# pwrconv.net
KiCad netlist of a schematic drawn in Altium Designer
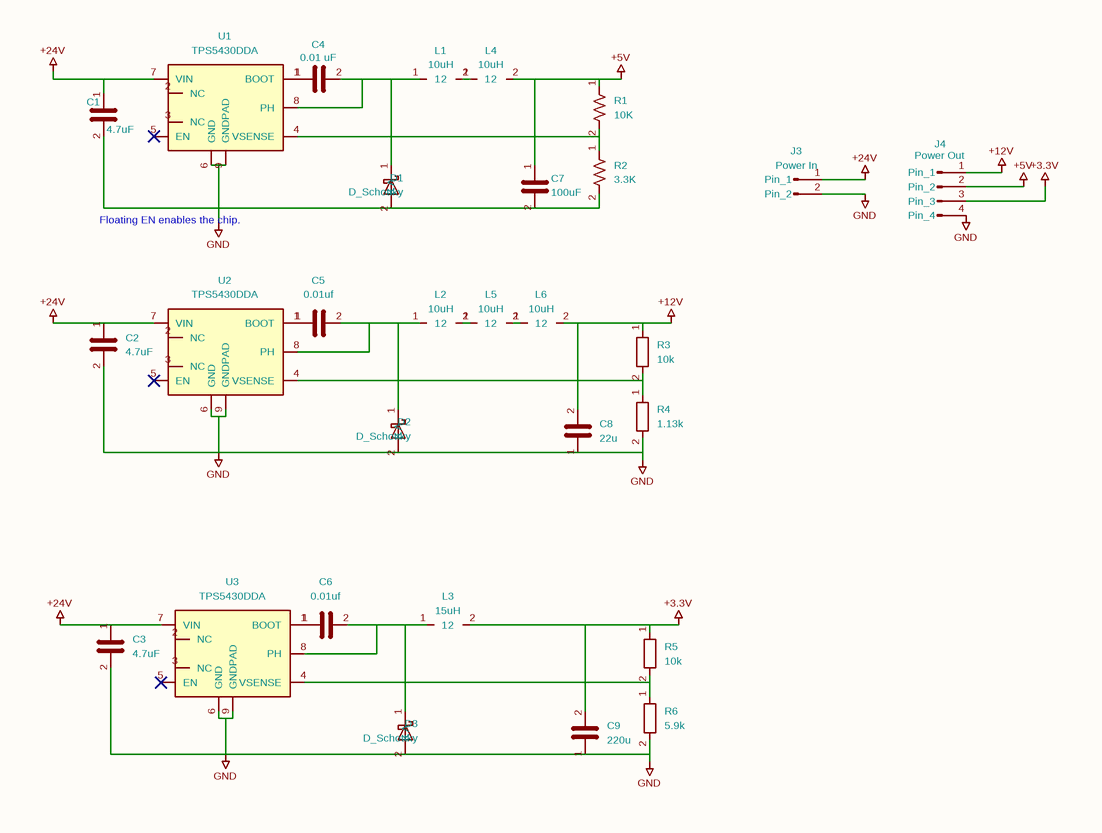
[diagram p0: pwrconv.SchDoc]

(export (version "E")
  (design (tool "Eeschema 10.0.6"))
  (components
    (comp (ref "C1")
      (value "4.7uF")
      (description "Unpolarized capacitor")
      (libsource (lib "Device") (part "C"))
    )
    (comp (ref "C2")
      (value "4.7uF")
      (description "Unpolarized Capacitor")
      (libsource (lib "Device") (part "C"))
    )
    (comp (ref "C3")
      (value "4.7uF")
      (description "Unpolarized Capacitor")
      (libsource (lib "Device") (part "C"))
    )
    (comp (ref "C4")
      (value "0.01 uF")
      (description "Unpolarized capacitor")
      (libsource (lib "Device") (part "C"))
    )
    (comp (ref "C5") (value "0.01uf") (libsource (lib "Device") (part "C")))
    (comp (ref "C6") (value "0.01uf") (libsource (lib "Device") (part "C")))
    (comp (ref "C7")
      (value "100uF")
      (description "Unpolarized capacitor")
      (libsource (lib "Device") (part "C"))
    )
    (comp (ref "C8") (value "22u") (libsource (lib "Device") (part "C")))
    (comp (ref "C9") (value "220u") (libsource (lib "Device") (part "C")))
    (comp (ref "D1")
      (value "D_Schottky")
      (description "Schottky diode")
      (libsource (lib "Device") (part "D_Schottky"))
    )
    (comp (ref "D2")
      (value "D_Schottky")
      (description "Schottky diode")
      (libsource (lib "Device") (part "D_Schottky"))
    )
    (comp (ref "D3")
      (value "D_Schottky")
      (description "Schottky diode")
      (libsource (lib "Device") (part "D_Schottky"))
    )
    (comp (ref "J3")
      (value "Power In")
      (description "Generic connector, single row, 01x02, script generated")
      (libsource (lib "Connector") (part "Conn_01x02_Pin"))
    )
    (comp (ref "J4")
      (value "Power Out")
      (description "Generic connector, single row, 01x04, script generated")
      (libsource (lib "Connector") (part "Conn_01x04_Pin"))
    )
    (comp (ref "L1") (value "10uH") (libsource (lib "Device") (part "L")))
    (comp (ref "L2") (value "10uH") (libsource (lib "Device") (part "L")))
    (comp (ref "L3") (value "15uH") (libsource (lib "Device") (part "L")))
    (comp (ref "L4") (value "10uH") (libsource (lib "Device") (part "L")))
    (comp (ref "L5") (value "10uH") (libsource (lib "Device") (part "L")))
    (comp (ref "L6") (value "10uH") (libsource (lib "Device") (part "L")))
    (comp (ref "R1")
      (value "10K")
      (description "Resistor, US symbol")
      (libsource (lib "Device") (part "R_US"))
    )
    (comp (ref "R2")
      (value "3.3K")
      (description "Resistor, US symbol")
      (libsource (lib "Device") (part "R_US"))
    )
    (comp (ref "R3") (value "10k") (libsource (lib "Device") (part "R")))
    (comp (ref "R4") (value "1.13k") (libsource (lib "Device") (part "R")))
    (comp (ref "R5") (value "10k") (libsource (lib "Device") (part "R")))
    (comp (ref "R6") (value "5.9k") (libsource (lib "Device") (part "R")))
    (comp (ref "U1")
      (value "TPS5430DDA")
      (description "3A, Step Down Swift Converter, Adjustable Output Voltage, 5.5-36V Input Voltage, PowerSO-8")
      (libsource (lib "Regulator_Switching") (part "TPS5430DDA"))
    )
    (comp (ref "U2") (value "TPS5430DDA") (libsource (lib "Regulator_Switching") (part "TPS5430DDA")))
    (comp (ref "U3") (value "TPS5430DDA") (libsource (lib "Regulator_Switching") (part "TPS5430DDA")))
  )
  (nets
    (net (code "1") (name "+3.3V") (class "Default")
      (node (ref "C9") (pin "2") (pinfunction "2_2") (pintype "passive"))
      (node (ref "J4") (pin "3") (pinfunction "Pin_3_3") (pintype "passive"))
      (node (ref "L3") (pin "2") (pinfunction "2_2") (pintype "passive"))
      (node (ref "R5") (pin "1") (pinfunction "1_1") (pintype "passive"))
    )
    (net (code "2") (name "+5V") (class "Default")
      (node (ref "C7") (pin "1") (pinfunction "1_1") (pintype "passive"))
      (node (ref "J4") (pin "2") (pinfunction "Pin_2_2") (pintype "passive"))
      (node (ref "L4") (pin "2") (pinfunction "2_2") (pintype "passive"))
      (node (ref "R1") (pin "1") (pinfunction "1_1") (pintype "passive"))
    )
    (net (code "3") (name "+12V") (class "Default")
      (node (ref "C8") (pin "2") (pinfunction "2_2") (pintype "passive"))
      (node (ref "J4") (pin "1") (pinfunction "Pin_1_1") (pintype "passive"))
      (node (ref "L6") (pin "2") (pinfunction "2_2") (pintype "passive"))
      (node (ref "R3") (pin "1") (pinfunction "1_1") (pintype "passive"))
    )
    (net (code "4") (name "+24V") (class "Default")
      (node (ref "C1") (pin "1") (pinfunction "1_1") (pintype "passive"))
      (node (ref "C2") (pin "1") (pinfunction "1_1") (pintype "passive"))
      (node (ref "C3") (pin "1") (pinfunction "1_1") (pintype "passive"))
      (node (ref "J3") (pin "1") (pinfunction "Pin_1_1") (pintype "passive"))
      (node (ref "U1") (pin "7") (pinfunction "VIN_7") (pintype "passive"))
      (node (ref "U2") (pin "7") (pinfunction "VIN_7") (pintype "passive"))
      (node (ref "U3") (pin "7") (pinfunction "VIN_7") (pintype "passive"))
    )
    (net (code "5") (name "GND") (class "Default")
      (node (ref "C1") (pin "2") (pinfunction "2_2") (pintype "passive"))
      (node (ref "C2") (pin "2") (pinfunction "2_2") (pintype "passive"))
      (node (ref "C3") (pin "2") (pinfunction "2_2") (pintype "passive"))
      (node (ref "C7") (pin "2") (pinfunction "2_2") (pintype "passive"))
      (node (ref "C8") (pin "1") (pinfunction "1_1") (pintype "passive"))
      (node (ref "C9") (pin "1") (pinfunction "1_1") (pintype "passive"))
      (node (ref "D1") (pin "2") (pinfunction "A_2") (pintype "passive"))
      (node (ref "D2") (pin "2") (pinfunction "A_2") (pintype "passive"))
      (node (ref "D3") (pin "2") (pinfunction "A_2") (pintype "passive"))
      (node (ref "J3") (pin "2") (pinfunction "Pin_2_2") (pintype "passive"))
      (node (ref "J4") (pin "4") (pinfunction "Pin_4_4") (pintype "passive"))
      (node (ref "R2") (pin "2") (pinfunction "2_2") (pintype "passive"))
      (node (ref "R4") (pin "2") (pinfunction "2_2") (pintype "passive"))
      (node (ref "R6") (pin "2") (pinfunction "2_2") (pintype "passive"))
      (node (ref "U1") (pin "6") (pinfunction "GND_6") (pintype "passive"))
      (node (ref "U1") (pin "9") (pinfunction "GNDPAD_9") (pintype "passive"))
      (node (ref "U2") (pin "6") (pinfunction "GND_6") (pintype "passive"))
      (node (ref "U2") (pin "9") (pinfunction "GNDPAD_9") (pintype "passive"))
      (node (ref "U3") (pin "6") (pinfunction "GND_6") (pintype "passive"))
      (node (ref "U3") (pin "9") (pinfunction "GNDPAD_9") (pintype "passive"))
    )
    (net (code "6") (name "Net-(D1-K)") (class "Default")
      (node (ref "C4") (pin "2") (pinfunction "2_2") (pintype "passive"))
      (node (ref "D1") (pin "1") (pinfunction "K_1") (pintype "passive"))
      (node (ref "L1") (pin "1") (pinfunction "1_1") (pintype "passive"))
      (node (ref "U1") (pin "8") (pinfunction "PH_8") (pintype "passive"))
    )
    (net (code "7") (name "Net-(D2-K)") (class "Default")
      (node (ref "C5") (pin "2") (pinfunction "2_2") (pintype "passive"))
      (node (ref "D2") (pin "1") (pinfunction "K_1") (pintype "passive"))
      (node (ref "L2") (pin "1") (pinfunction "1_1") (pintype "passive"))
      (node (ref "U2") (pin "8") (pinfunction "PH_8") (pintype "passive"))
    )
    (net (code "8") (name "Net-(D3-K)") (class "Default")
      (node (ref "C6") (pin "2") (pinfunction "2_2") (pintype "passive"))
      (node (ref "D3") (pin "1") (pinfunction "K_1") (pintype "passive"))
      (node (ref "L3") (pin "1") (pinfunction "1_1") (pintype "passive"))
      (node (ref "U3") (pin "8") (pinfunction "PH_8") (pintype "passive"))
    )
    (net (code "9") (name "Net-(L1-Pad2)") (class "Default")
      (node (ref "L1") (pin "2") (pinfunction "2_2") (pintype "passive"))
      (node (ref "L4") (pin "1") (pinfunction "1_1") (pintype "passive"))
    )
    (net (code "10") (name "Net-(L2-Pad2)") (class "Default")
      (node (ref "L2") (pin "2") (pinfunction "2_2") (pintype "passive"))
      (node (ref "L5") (pin "1") (pinfunction "1_1") (pintype "passive"))
    )
    (net (code "11") (name "Net-(L5-Pad2)") (class "Default")
      (node (ref "L5") (pin "2") (pinfunction "2_2") (pintype "passive"))
      (node (ref "L6") (pin "1") (pinfunction "1_1") (pintype "passive"))
    )
    (net (code "12") (name "Net-(U1-BOOT)") (class "Default")
      (node (ref "C4") (pin "1") (pinfunction "1_1") (pintype "passive"))
      (node (ref "U1") (pin "1") (pinfunction "BOOT_1") (pintype "passive"))
    )
    (net (code "13") (name "Net-(U1-VSENSE)") (class "Default")
      (node (ref "R1") (pin "2") (pinfunction "2_2") (pintype "passive"))
      (node (ref "R2") (pin "1") (pinfunction "1_1") (pintype "passive"))
      (node (ref "U1") (pin "4") (pinfunction "VSENSE_4") (pintype "passive"))
    )
    (net (code "14") (name "Net-(U2-BOOT)") (class "Default")
      (node (ref "C5") (pin "1") (pinfunction "1_1") (pintype "passive"))
      (node (ref "U2") (pin "1") (pinfunction "BOOT_1") (pintype "passive"))
    )
    (net (code "15") (name "Net-(U2-VSENSE)") (class "Default")
      (node (ref "R3") (pin "2") (pinfunction "2_2") (pintype "passive"))
      (node (ref "R4") (pin "1") (pinfunction "1_1") (pintype "passive"))
      (node (ref "U2") (pin "4") (pinfunction "VSENSE_4") (pintype "passive"))
    )
    (net (code "16") (name "Net-(U3-BOOT)") (class "Default")
      (node (ref "C6") (pin "1") (pinfunction "1_1") (pintype "passive"))
      (node (ref "U3") (pin "1") (pinfunction "BOOT_1") (pintype "passive"))
    )
    (net (code "17") (name "Net-(U3-VSENSE)") (class "Default")
      (node (ref "R5") (pin "2") (pinfunction "2_2") (pintype "passive"))
      (node (ref "R6") (pin "1") (pinfunction "1_1") (pintype "passive"))
      (node (ref "U3") (pin "4") (pinfunction "VSENSE_4") (pintype "passive"))
    )
    (net (code "18") (name "unconnected-(U1-EN-Pad5)") (class "Default")
      (node (ref "U1") (pin "5") (pinfunction "EN_5") (pintype "passive+no_connect"))
    )
    (net (code "19") (name "unconnected-(U1-NC-Pad2)") (class "Default")
      (node (ref "U1") (pin "2") (pinfunction "NC_2") (pintype "passive"))
    )
    (net (code "20") (name "unconnected-(U1-NC-Pad3)") (class "Default")
      (node (ref "U1") (pin "3") (pinfunction "NC_3") (pintype "passive"))
    )
    (net (code "21") (name "unconnected-(U2-EN-Pad5)") (class "Default")
      (node (ref "U2") (pin "5") (pinfunction "EN_5") (pintype "passive+no_connect"))
    )
    (net (code "22") (name "unconnected-(U2-NC-Pad2)") (class "Default")
      (node (ref "U2") (pin "2") (pinfunction "NC_2") (pintype "passive"))
    )
    (net (code "23") (name "unconnected-(U2-NC-Pad3)") (class "Default")
      (node (ref "U2") (pin "3") (pinfunction "NC_3") (pintype "passive"))
    )
    (net (code "24") (name "unconnected-(U3-EN-Pad5)") (class "Default")
      (node (ref "U3") (pin "5") (pinfunction "EN_5") (pintype "passive+no_connect"))
    )
    (net (code "25") (name "unconnected-(U3-NC-Pad2)") (class "Default")
      (node (ref "U3") (pin "2") (pinfunction "NC_2") (pintype "passive"))
    )
    (net (code "26") (name "unconnected-(U3-NC-Pad3)") (class "Default")
      (node (ref "U3") (pin "3") (pinfunction "NC_3") (pintype "passive"))
    )
  )
)
